# Pi2RMini_v1_0.net
KiCad netlist of a schematic drawn in EAGLE
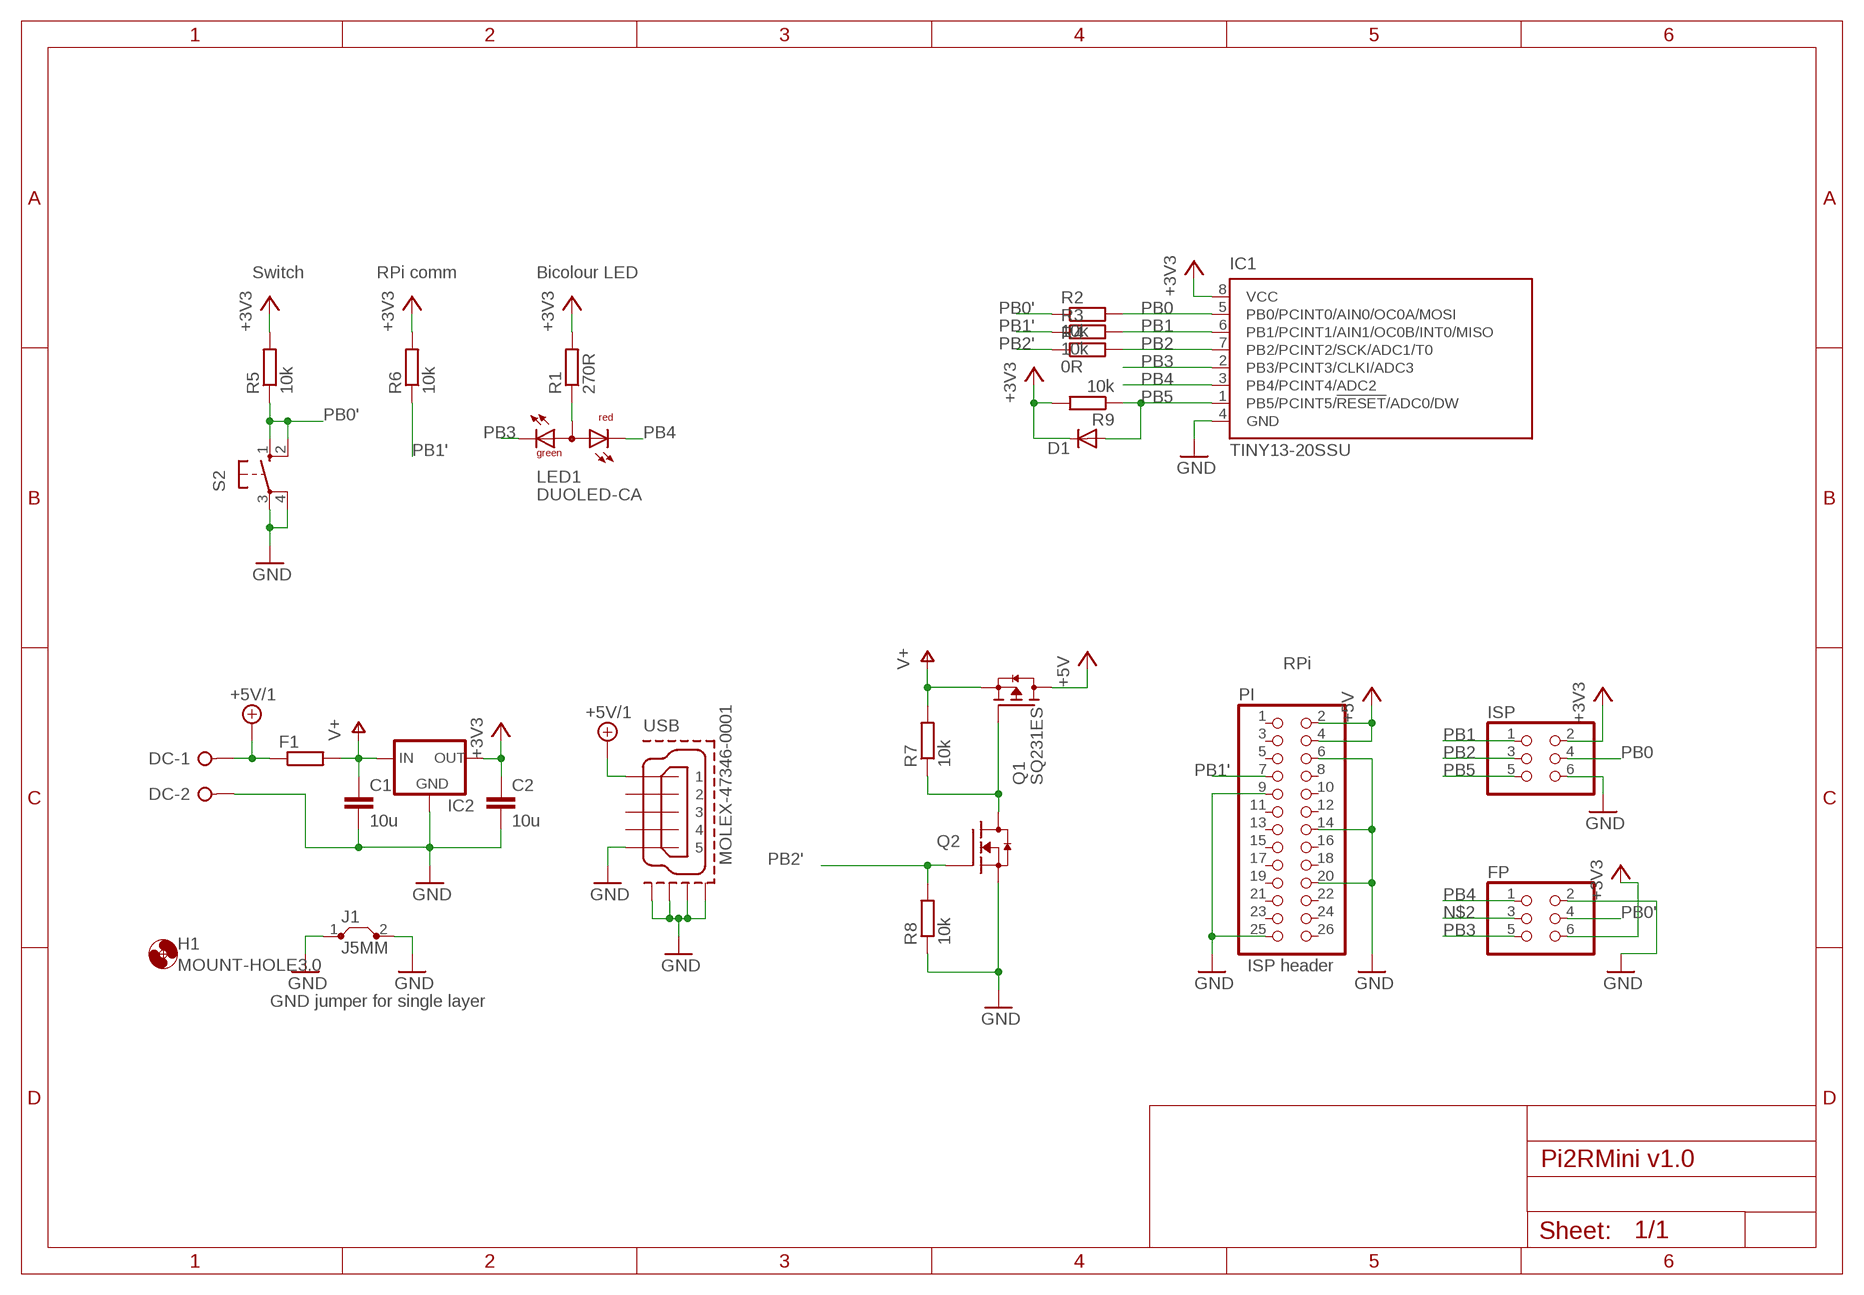
[diagram p0: schematic, sheet 1]

(export (version "E")
  (design (tool "Eeschema 10.0.6"))
  (components
    (comp (ref "C1")
      (value "10u")
      (footprint "eagle-import:C0805")
      (libsource (lib "eagle-import") (part "C-EUC0805"))
    )
    (comp (ref "C2")
      (value "10u")
      (footprint "eagle-import:C0805")
      (libsource (lib "eagle-import") (part "C-EUC0805"))
    )
    (comp (ref "D1")
      (value "DIODE-MICROMELF-R")
      (footprint "eagle-import:MICROMELF-R")
      (libsource (lib "eagle-import") (part "DIODE-MICROMELF-R"))
    )
    (comp (ref "DC")
      (value "W237-02P")
      (footprint "eagle-import:W237-132")
      (libsource (lib "eagle-import") (part "W237-02P"))
    )
    (comp (ref "F1")
      (value "R-EU_R1210")
      (footprint "eagle-import:R1210")
      (libsource (lib "eagle-import") (part "R-EU_R1210"))
    )
    (comp (ref "FP")
      (value "PINHD-2X3")
      (footprint "eagle-import:2X03")
      (libsource (lib "eagle-import") (part "PINHD-2X3"))
    )
    (comp (ref "H1")
      (value "MOUNT-HOLE3.0")
      (footprint "eagle-import:3,0")
      (libsource (lib "eagle-import") (part "MOUNT-HOLE3.0"))
    )
    (comp (ref "IC1")
      (value "TINY13-20SSU")
      (footprint "eagle-import:8S1")
      (fields (field (name "MPN") "ATTINY13-20SSU"))
      (libsource (lib "eagle-import") (part "TINY13SSU-20"))
    )
    (comp (ref "IC2")
      (value "MCP1700TT")
      (footprint "eagle-import:SOT-23")
      (libsource (lib "eagle-import") (part "MCP1700TT"))
    )
    (comp (ref "ISP")
      (value "PINHD-2X3")
      (footprint "eagle-import:2X03")
      (libsource (lib "eagle-import") (part "PINHD-2X3"))
    )
    (comp (ref "J1")
      (value "J5MM")
      (footprint "eagle-import:05")
      (libsource (lib "eagle-import") (part "J5MM"))
    )
    (comp (ref "LED1")
      (value "DUOLED-CA")
      (footprint "eagle-import:SOT-23")
      (libsource (lib "eagle-import") (part "DUOLED-CA"))
    )
    (comp (ref "PI")
      (value "PINHD-2X13")
      (footprint "eagle-import:2X13")
      (libsource (lib "eagle-import") (part "PINHD-2X13"))
    )
    (comp (ref "Q1")
      (value "SQ231ES")
      (footprint "eagle-import:SOT-23")
      (libsource (lib "eagle-import") (part "SQ231ES"))
    )
    (comp (ref "Q2")
      (value "2N7002")
      (footprint "eagle-import:SOT-23")
      (libsource (lib "eagle-import") (part "2N7002"))
    )
    (comp (ref "R1")
      (value "270R")
      (footprint "eagle-import:R0805")
      (libsource (lib "eagle-import") (part "R-EU_R0805"))
    )
    (comp (ref "R2")
      (value "10k")
      (footprint "eagle-import:R0805")
      (libsource (lib "eagle-import") (part "R-EU_R0805"))
    )
    (comp (ref "R3")
      (value "10k")
      (footprint "eagle-import:R0805")
      (libsource (lib "eagle-import") (part "R-EU_R0805"))
    )
    (comp (ref "R4")
      (value "0R")
      (footprint "eagle-import:R0805")
      (libsource (lib "eagle-import") (part "R-EU_R0805"))
    )
    (comp (ref "R5")
      (value "10k")
      (footprint "eagle-import:R0805")
      (libsource (lib "eagle-import") (part "R-EU_R0805"))
    )
    (comp (ref "R6")
      (value "10k")
      (footprint "eagle-import:R0805")
      (libsource (lib "eagle-import") (part "R-EU_R0805"))
    )
    (comp (ref "R7")
      (value "10k")
      (footprint "eagle-import:R0805")
      (libsource (lib "eagle-import") (part "R-EU_R0805"))
    )
    (comp (ref "R8")
      (value "10k")
      (footprint "eagle-import:R0805")
      (libsource (lib "eagle-import") (part "R-EU_R0805"))
    )
    (comp (ref "R9")
      (value "10k")
      (footprint "eagle-import:R0805")
      (libsource (lib "eagle-import") (part "R-EU_R0805"))
    )
    (comp (ref "S2")
      (value "10-XX")
      (footprint "eagle-import:B3F-10XX")
      (fields (field (name "MPN") "B3F-1000"))
      (libsource (lib "eagle-import") (part "10-XX"))
    )
    (comp (ref "USB")
      (value "MOLEX-47346-0001")
      (footprint "eagle-import:MOLEX-47364-0001")
      (libsource (lib "eagle-import") (part "MOLEX-47346-0001"))
    )
  )
  (nets
    (net (code "1") (name "+3V3") (class "Default")
      (node (ref "C2") (pin "1") (pinfunction "1_1") (pintype "passive"))
      (node (ref "D1") (pin "C") (pinfunction "C_C") (pintype "passive"))
      (node (ref "FP") (pin "6") (pinfunction "6_6") (pintype "passive"))
      (node (ref "IC1") (pin "8") (pinfunction "VCC_8") (pintype "power_in"))
      (node (ref "IC2") (pin "2") (pinfunction "OUT_2") (pintype "passive"))
      (node (ref "ISP") (pin "2") (pinfunction "2_2") (pintype "passive"))
      (node (ref "R1") (pin "2") (pinfunction "2_2") (pintype "passive"))
      (node (ref "R5") (pin "2") (pinfunction "2_2") (pintype "passive"))
      (node (ref "R6") (pin "2") (pinfunction "2_2") (pintype "passive"))
      (node (ref "R9") (pin "2") (pinfunction "2_2") (pintype "passive"))
    )
    (net (code "2") (name "+5V") (class "Default")
      (node (ref "PI") (pin "2") (pinfunction "2_2") (pintype "passive"))
      (node (ref "PI") (pin "4") (pinfunction "4_4") (pintype "passive"))
      (node (ref "Q1") (pin "3") (pinfunction "D_3") (pintype "passive"))
    )
    (net (code "3") (name "+5V{slash}1") (class "Default")
      (node (ref "DC") (pin "1") (pinfunction "KL_1") (pintype "passive"))
      (node (ref "F1") (pin "1") (pinfunction "1_1") (pintype "passive"))
      (node (ref "USB") (pin "1") (pinfunction "1_1") (pintype "input"))
    )
    (net (code "4") (name "/N$2") (class "Default")
      (node (ref "FP") (pin "3") (pinfunction "3_3") (pintype "passive"))
      (node (ref "LED1") (pin "3") (pinfunction "A_3") (pintype "passive"))
      (node (ref "R1") (pin "1") (pinfunction "1_1") (pintype "passive"))
    )
    (net (code "5") (name "/PB0") (class "Default")
      (node (ref "IC1") (pin "5") (pinfunction "PB0/PCINT0/AIN0/OC0A/MOSI_5") (pintype "bidirectional"))
      (node (ref "ISP") (pin "4") (pinfunction "4_4") (pintype "passive"))
      (node (ref "R2") (pin "2") (pinfunction "2_2") (pintype "passive"))
    )
    (net (code "6") (name "/PB0'") (class "Default")
      (node (ref "FP") (pin "4") (pinfunction "4_4") (pintype "passive"))
      (node (ref "R2") (pin "1") (pinfunction "1_1") (pintype "passive"))
      (node (ref "R5") (pin "1") (pinfunction "1_1") (pintype "passive"))
      (node (ref "S2") (pin "1") (pinfunction "S_1") (pintype "passive"))
      (node (ref "S2") (pin "2") (pinfunction "S1_2") (pintype "passive"))
    )
    (net (code "7") (name "/PB1") (class "Default")
      (node (ref "IC1") (pin "6") (pinfunction "PB1/PCINT1/AIN1/OC0B/INT0/MISO_6") (pintype "bidirectional"))
      (node (ref "ISP") (pin "1") (pinfunction "1_1") (pintype "passive"))
      (node (ref "R3") (pin "2") (pinfunction "2_2") (pintype "passive"))
    )
    (net (code "8") (name "/PB1'") (class "Default")
      (node (ref "PI") (pin "7") (pinfunction "7_7") (pintype "passive"))
      (node (ref "R3") (pin "1") (pinfunction "1_1") (pintype "passive"))
      (node (ref "R6") (pin "1") (pinfunction "1_1") (pintype "passive"))
    )
    (net (code "9") (name "/PB2") (class "Default")
      (node (ref "IC1") (pin "7") (pinfunction "PB2/PCINT2/SCK/ADC1/T0_7") (pintype "bidirectional"))
      (node (ref "ISP") (pin "3") (pinfunction "3_3") (pintype "passive"))
      (node (ref "R4") (pin "2") (pinfunction "2_2") (pintype "passive"))
    )
    (net (code "10") (name "/PB2'") (class "Default")
      (node (ref "Q2") (pin "1") (pinfunction "G_1") (pintype "passive"))
      (node (ref "R4") (pin "1") (pinfunction "1_1") (pintype "passive"))
      (node (ref "R8") (pin "2") (pinfunction "2_2") (pintype "passive"))
    )
    (net (code "11") (name "/PB3") (class "Default")
      (node (ref "FP") (pin "5") (pinfunction "5_5") (pintype "passive"))
      (node (ref "IC1") (pin "2") (pinfunction "PB3/PCINT3/CLKI/ADC3_2") (pintype "bidirectional"))
      (node (ref "LED1") (pin "2") (pinfunction "CG_2") (pintype "passive"))
    )
    (net (code "12") (name "/PB4") (class "Default")
      (node (ref "FP") (pin "1") (pinfunction "1_1") (pintype "passive"))
      (node (ref "IC1") (pin "3") (pinfunction "PB4/PCINT4/ADC2_3") (pintype "bidirectional"))
      (node (ref "LED1") (pin "1") (pinfunction "CR_1") (pintype "passive"))
    )
    (net (code "13") (name "/PB5") (class "Default")
      (node (ref "D1") (pin "A") (pinfunction "A_A") (pintype "passive"))
      (node (ref "IC1") (pin "1") (pinfunction "PB5/PCINT5/~{RESET}/ADC0/DW_1") (pintype "bidirectional"))
      (node (ref "ISP") (pin "5") (pinfunction "5_5") (pintype "passive"))
      (node (ref "R9") (pin "1") (pinfunction "1_1") (pintype "passive"))
    )
    (net (code "14") (name "GND") (class "Default")
      (node (ref "C1") (pin "2") (pinfunction "2_2") (pintype "passive"))
      (node (ref "C2") (pin "2") (pinfunction "2_2") (pintype "passive"))
      (node (ref "DC") (pin "2") (pinfunction "KL_2") (pintype "passive"))
      (node (ref "FP") (pin "2") (pinfunction "2_2") (pintype "passive"))
      (node (ref "IC1") (pin "4") (pinfunction "GND_4") (pintype "power_in"))
      (node (ref "IC2") (pin "1") (pinfunction "GND_1") (pintype "input"))
      (node (ref "ISP") (pin "6") (pinfunction "6_6") (pintype "passive"))
      (node (ref "J1") (pin "1") (pinfunction "1_1") (pintype "passive"))
      (node (ref "J1") (pin "2") (pinfunction "2_2") (pintype "passive"))
      (node (ref "PI") (pin "14") (pinfunction "14_14") (pintype "passive"))
      (node (ref "PI") (pin "20") (pinfunction "20_20") (pintype "passive"))
      (node (ref "PI") (pin "25") (pinfunction "25_25") (pintype "passive"))
      (node (ref "PI") (pin "6") (pinfunction "6_6") (pintype "passive"))
      (node (ref "PI") (pin "9") (pinfunction "9_9") (pintype "passive"))
      (node (ref "Q2") (pin "2") (pinfunction "S_2") (pintype "passive"))
      (node (ref "R8") (pin "1") (pinfunction "1_1") (pintype "passive"))
      (node (ref "S2") (pin "3") (pinfunction "P_3") (pintype "passive"))
      (node (ref "S2") (pin "4") (pinfunction "P1_4") (pintype "passive"))
      (node (ref "USB") (pin "5") (pinfunction "5_5") (pintype "input"))
      (node (ref "USB") (pin "GND1") (pinfunction "GND1_GND1") (pintype "bidirectional"))
      (node (ref "USB") (pin "GND2") (pinfunction "GND2_GND2") (pintype "bidirectional"))
      (node (ref "USB") (pin "GND3") (pinfunction "GND3_GND3") (pintype "bidirectional"))
      (node (ref "USB") (pin "GND4") (pinfunction "GND4_GND4") (pintype "bidirectional"))
    )
    (net (code "15") (name "Net-(Q1-G)") (class "Default")
      (node (ref "Q1") (pin "1") (pinfunction "G_1") (pintype "passive"))
      (node (ref "Q2") (pin "3") (pinfunction "D_3") (pintype "passive"))
      (node (ref "R7") (pin "1") (pinfunction "1_1") (pintype "passive"))
    )
    (net (code "16") (name "V+") (class "Default")
      (node (ref "C1") (pin "1") (pinfunction "1_1") (pintype "passive"))
      (node (ref "F1") (pin "2") (pinfunction "2_2") (pintype "passive"))
      (node (ref "IC2") (pin "3") (pinfunction "IN_3") (pintype "input"))
      (node (ref "Q1") (pin "2") (pinfunction "S_2") (pintype "passive"))
      (node (ref "R7") (pin "2") (pinfunction "2_2") (pintype "passive"))
    )
    (net (code "17") (name "unconnected-(PI-Pad1)") (class "Default")
      (node (ref "PI") (pin "1") (pinfunction "1_1") (pintype "passive"))
    )
    (net (code "18") (name "unconnected-(PI-Pad3)") (class "Default")
      (node (ref "PI") (pin "3") (pinfunction "3_3") (pintype "passive"))
    )
    (net (code "19") (name "unconnected-(PI-Pad5)") (class "Default")
      (node (ref "PI") (pin "5") (pinfunction "5_5") (pintype "passive"))
    )
    (net (code "20") (name "unconnected-(PI-Pad8)") (class "Default")
      (node (ref "PI") (pin "8") (pinfunction "8_8") (pintype "passive"))
    )
    (net (code "21") (name "unconnected-(PI-Pad10)") (class "Default")
      (node (ref "PI") (pin "10") (pinfunction "10_10") (pintype "passive"))
    )
    (net (code "22") (name "unconnected-(PI-Pad11)") (class "Default")
      (node (ref "PI") (pin "11") (pinfunction "11_11") (pintype "passive"))
    )
    (net (code "23") (name "unconnected-(PI-Pad12)") (class "Default")
      (node (ref "PI") (pin "12") (pinfunction "12_12") (pintype "passive"))
    )
    (net (code "24") (name "unconnected-(PI-Pad13)") (class "Default")
      (node (ref "PI") (pin "13") (pinfunction "13_13") (pintype "passive"))
    )
    (net (code "25") (name "unconnected-(PI-Pad15)") (class "Default")
      (node (ref "PI") (pin "15") (pinfunction "15_15") (pintype "passive"))
    )
    (net (code "26") (name "unconnected-(PI-Pad16)") (class "Default")
      (node (ref "PI") (pin "16") (pinfunction "16_16") (pintype "passive"))
    )
    (net (code "27") (name "unconnected-(PI-Pad17)") (class "Default")
      (node (ref "PI") (pin "17") (pinfunction "17_17") (pintype "passive"))
    )
    (net (code "28") (name "unconnected-(PI-Pad18)") (class "Default")
      (node (ref "PI") (pin "18") (pinfunction "18_18") (pintype "passive"))
    )
    (net (code "29") (name "unconnected-(PI-Pad19)") (class "Default")
      (node (ref "PI") (pin "19") (pinfunction "19_19") (pintype "passive"))
    )
    (net (code "30") (name "unconnected-(PI-Pad21)") (class "Default")
      (node (ref "PI") (pin "21") (pinfunction "21_21") (pintype "passive"))
    )
    (net (code "31") (name "unconnected-(PI-Pad22)") (class "Default")
      (node (ref "PI") (pin "22") (pinfunction "22_22") (pintype "passive"))
    )
    (net (code "32") (name "unconnected-(PI-Pad23)") (class "Default")
      (node (ref "PI") (pin "23") (pinfunction "23_23") (pintype "passive"))
    )
    (net (code "33") (name "unconnected-(PI-Pad24)") (class "Default")
      (node (ref "PI") (pin "24") (pinfunction "24_24") (pintype "passive"))
    )
    (net (code "34") (name "unconnected-(PI-Pad26)") (class "Default")
      (node (ref "PI") (pin "26") (pinfunction "26_26") (pintype "passive"))
    )
    (net (code "35") (name "unconnected-(USB-Pad2)") (class "Default")
      (node (ref "USB") (pin "2") (pinfunction "2_2") (pintype "input"))
    )
    (net (code "36") (name "unconnected-(USB-Pad3)") (class "Default")
      (node (ref "USB") (pin "3") (pinfunction "3_3") (pintype "input"))
    )
    (net (code "37") (name "unconnected-(USB-Pad4)") (class "Default")
      (node (ref "USB") (pin "4") (pinfunction "4_4") (pintype "input"))
    )
  )
)
